# Module.net
KiCad netlist of a schematic drawn in Altium Designer
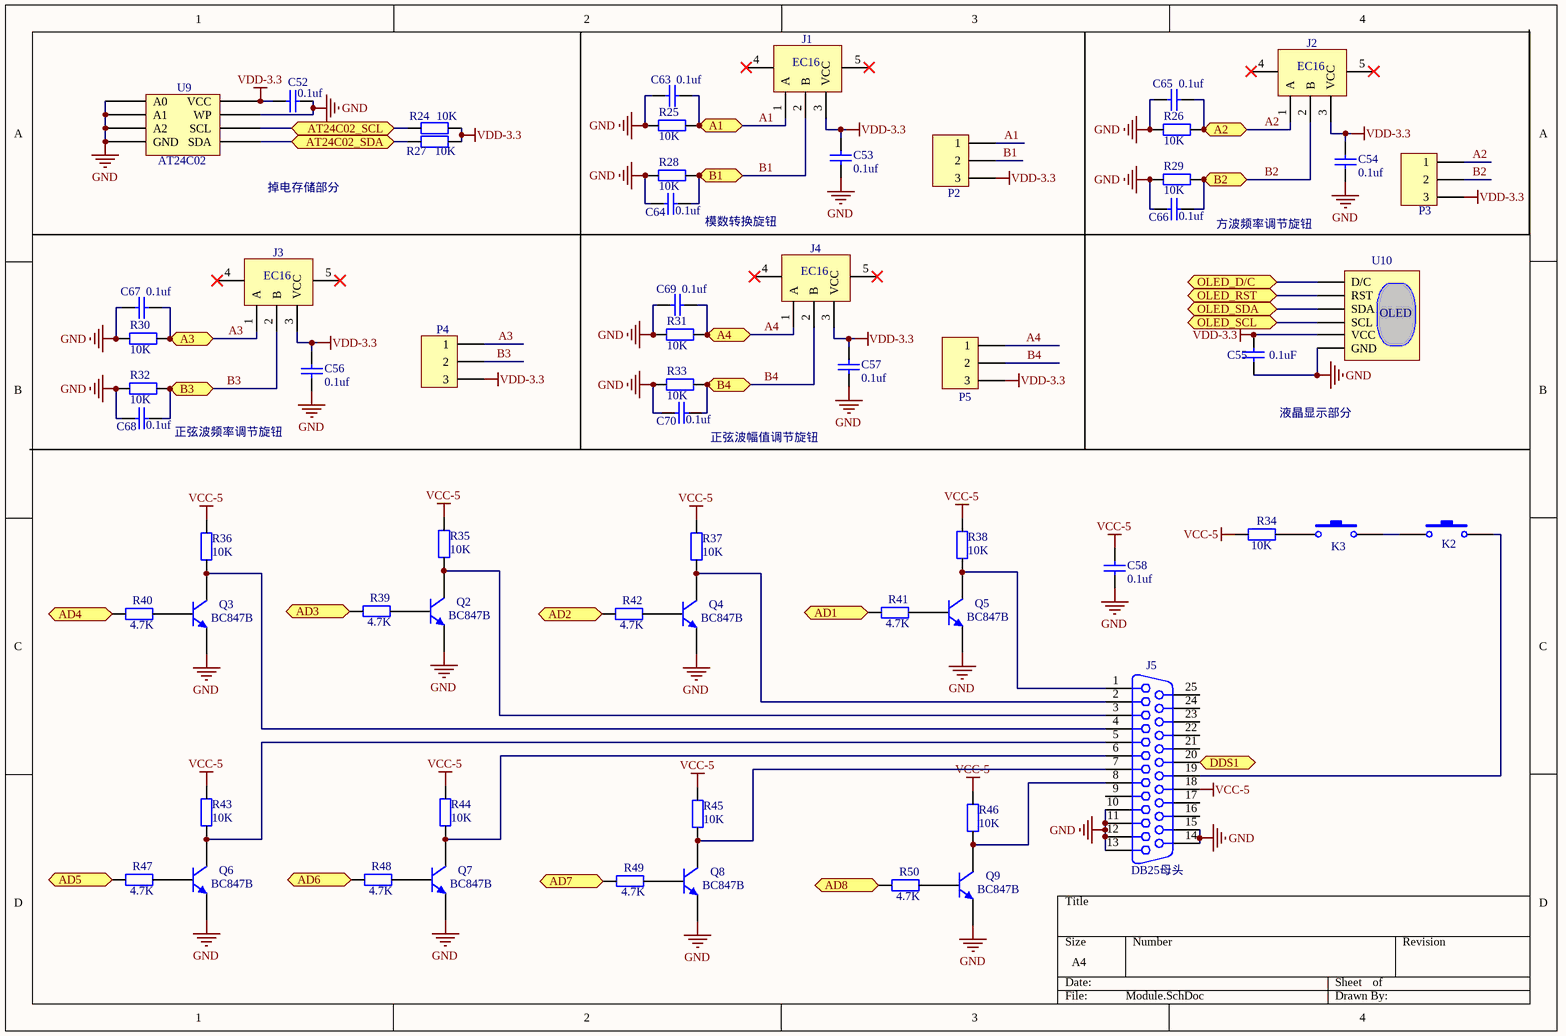
[diagram p0: Module.SchDoc]

(export (version "E")
  (design (tool "Eeschema 10.0.6"))
  (components
    (comp (ref "C52")
      (value "0.1uf")
      (footprint "0603")
      (fields (field (name "Comment") "Capacitor-0603"))
      (libsource (lib "原理图库") (part "Capacitor-0603"))
    )
    (comp (ref "C53")
      (value "0.1uf")
      (footprint "0603")
      (fields (field (name "Comment") "Capacitor-0603"))
      (libsource (lib "原理图库") (part "Capacitor-0603"))
    )
    (comp (ref "C54")
      (value "0.1uf")
      (footprint "0603")
      (fields (field (name "Comment") "Capacitor-0603"))
      (libsource (lib "原理图库") (part "Capacitor-0603"))
    )
    (comp (ref "C55")
      (value "0.1uF")
      (footprint "0603")
      (fields (field (name "Comment") "Capacitor-0805"))
      (libsource (lib "原理图库") (part "Capacitor-0805"))
    )
    (comp (ref "C56")
      (value "0.1uf")
      (footprint "0603")
      (fields (field (name "Comment") "Capacitor-0603"))
      (libsource (lib "原理图库") (part "Capacitor-0603"))
    )
    (comp (ref "C57")
      (value "0.1uf")
      (footprint "0603")
      (fields (field (name "Comment") "Capacitor-0603"))
      (libsource (lib "原理图库") (part "Capacitor-0603"))
    )
    (comp (ref "C58")
      (value "0.1uf")
      (footprint "0603")
      (fields (field (name "Comment") "Capacitor-0603"))
      (libsource (lib "原理图库") (part "Capacitor-0603"))
    )
    (comp (ref "C63")
      (value "0.1uf")
      (footprint "0603")
      (fields (field (name "Comment") "Capacitor-0603"))
      (libsource (lib "原理图库") (part "Capacitor-0603"))
    )
    (comp (ref "C64")
      (value "0.1uf")
      (footprint "0603")
      (fields (field (name "Comment") "Capacitor-0603"))
      (libsource (lib "原理图库") (part "Capacitor-0603"))
    )
    (comp (ref "C65")
      (value "0.1uf")
      (footprint "0603")
      (fields (field (name "Comment") "Capacitor-0603"))
      (libsource (lib "原理图库") (part "Capacitor-0603"))
    )
    (comp (ref "C66")
      (value "0.1uf")
      (footprint "0603")
      (fields (field (name "Comment") "Capacitor-0603"))
      (libsource (lib "原理图库") (part "Capacitor-0603"))
    )
    (comp (ref "C67")
      (value "0.1uf")
      (footprint "0603")
      (fields (field (name "Comment") "Capacitor-0603"))
      (libsource (lib "原理图库") (part "Capacitor-0603"))
    )
    (comp (ref "C68")
      (value "0.1uf")
      (footprint "0603")
      (fields (field (name "Comment") "Capacitor-0603"))
      (libsource (lib "原理图库") (part "Capacitor-0603"))
    )
    (comp (ref "C69")
      (value "0.1uf")
      (footprint "0603")
      (fields (field (name "Comment") "Capacitor-0603"))
      (libsource (lib "原理图库") (part "Capacitor-0603"))
    )
    (comp (ref "C70")
      (value "0.1uf")
      (footprint "0603")
      (fields (field (name "Comment") "Capacitor-0603"))
      (libsource (lib "原理图库") (part "Capacitor-0603"))
    )
    (comp (ref "J1")
      (value "EC16编码器")
      (footprint "EC16")
      (fields (field (name "NAME") "EC16"))
      (libsource (lib "原理图库") (part "EC16编码器"))
    )
    (comp (ref "J2")
      (value "EC16编码器")
      (footprint "EC16")
      (fields (field (name "NAME") "EC16"))
      (libsource (lib "原理图库") (part "EC16编码器"))
    )
    (comp (ref "J3")
      (value "EC16编码器")
      (footprint "EC16")
      (fields (field (name "NAME") "EC16"))
      (libsource (lib "原理图库") (part "EC16编码器"))
    )
    (comp (ref "J4")
      (value "EC16编码器")
      (footprint "EC16")
      (fields (field (name "NAME") "EC16"))
      (libsource (lib "原理图库") (part "EC16编码器"))
    )
    (comp (ref "J5")
      (value "DB25母头")
      (footprint "DB25母头")
      (fields (field (name "Comment") "DB25"))
      (libsource (lib "原理图库") (part "DB25"))
    )
    (comp (ref "K2") (value "按键") (footprint "2MM接线端子") (libsource (lib "原理图库") (part "按键")))
    (comp (ref "K3") (value "按键") (footprint "2MM接线端子") (libsource (lib "原理图库") (part "按键")))
    (comp (ref "P2") (value "端子3") (footprint "3MM接线端子") (libsource (lib "原理图库") (part "端子3")))
    (comp (ref "P3") (value "端子3") (footprint "3MM接线端子") (libsource (lib "原理图库") (part "端子3")))
    (comp (ref "P4") (value "端子3") (footprint "3MM接线端子") (libsource (lib "原理图库") (part "端子3")))
    (comp (ref "P5") (value "端子3") (footprint "3MM接线端子") (libsource (lib "原理图库") (part "端子3")))
    (comp (ref "Q2")
      (value "BC847")
      (footprint "BC847B")
      (fields (field (name "NAME") "BC847B"))
      (libsource (lib "原理图库") (part "BC847"))
    )
    (comp (ref "Q3")
      (value "BC847")
      (footprint "BC847B")
      (fields (field (name "NAME") "BC847B"))
      (libsource (lib "原理图库") (part "BC847"))
    )
    (comp (ref "Q4")
      (value "BC847")
      (footprint "BC847B")
      (fields (field (name "NAME") "BC847B"))
      (libsource (lib "原理图库") (part "BC847"))
    )
    (comp (ref "Q5")
      (value "BC847")
      (footprint "BC847B")
      (fields (field (name "NAME") "BC847B"))
      (libsource (lib "原理图库") (part "BC847"))
    )
    (comp (ref "Q6")
      (value "BC847")
      (footprint "BC847B")
      (fields (field (name "NAME") "BC847B"))
      (libsource (lib "原理图库") (part "BC847"))
    )
    (comp (ref "Q7")
      (value "BC847")
      (footprint "BC847B")
      (fields (field (name "NAME") "BC847B"))
      (libsource (lib "原理图库") (part "BC847"))
    )
    (comp (ref "Q8")
      (value "BC847")
      (footprint "BC847B")
      (fields (field (name "NAME") "BC847B"))
      (libsource (lib "原理图库") (part "BC847"))
    )
    (comp (ref "Q9")
      (value "BC847")
      (footprint "BC847B")
      (fields (field (name "NAME") "BC847B"))
      (libsource (lib "原理图库") (part "BC847"))
    )
    (comp (ref "R24")
      (value "10K")
      (footprint "0603")
      (fields (field (name "Comment") "Resistor-0603"))
      (libsource (lib "原理图库") (part "Resistor-0603"))
    )
    (comp (ref "R25")
      (value "10K")
      (footprint "0603")
      (fields (field (name "Comment") "Resistor-0603"))
      (libsource (lib "") (part "Resistor-0603_1"))
    )
    (comp (ref "R26")
      (value "10K")
      (footprint "0603")
      (fields (field (name "Comment") "Resistor-0603"))
      (libsource (lib "") (part "Resistor-0603_1"))
    )
    (comp (ref "R27")
      (value "10K")
      (footprint "0603")
      (fields (field (name "Comment") "Resistor-0603"))
      (libsource (lib "原理图库") (part "Resistor-0603"))
    )
    (comp (ref "R28")
      (value "10K")
      (footprint "0603")
      (fields (field (name "Comment") "Resistor-0603"))
      (libsource (lib "") (part "Resistor-0603_1"))
    )
    (comp (ref "R29")
      (value "10K")
      (footprint "0603")
      (fields (field (name "Comment") "Resistor-0603"))
      (libsource (lib "") (part "Resistor-0603_1"))
    )
    (comp (ref "R30")
      (value "10K")
      (footprint "0603")
      (fields (field (name "Comment") "Resistor-0603"))
      (libsource (lib "") (part "Resistor-0603_1"))
    )
    (comp (ref "R31")
      (value "10K")
      (footprint "0603")
      (fields (field (name "Comment") "Resistor-0603"))
      (libsource (lib "") (part "Resistor-0603_1"))
    )
    (comp (ref "R32")
      (value "10K")
      (footprint "0603")
      (fields (field (name "Comment") "Resistor-0603"))
      (libsource (lib "") (part "Resistor-0603_1"))
    )
    (comp (ref "R33")
      (value "10K")
      (footprint "0603")
      (fields (field (name "Comment") "Resistor-0603"))
      (libsource (lib "") (part "Resistor-0603_1"))
    )
    (comp (ref "R34")
      (value "10K")
      (footprint "0603")
      (fields (field (name "Comment") "Resistor-0603"))
      (libsource (lib "") (part "Resistor-0603_1"))
    )
    (comp (ref "R35")
      (value "10K")
      (footprint "0603")
      (fields (field (name "Comment") "Resistor-0603"))
      (libsource (lib "") (part "Resistor-0603_2"))
    )
    (comp (ref "R36")
      (value "10K")
      (footprint "0603")
      (fields (field (name "Comment") "Resistor-0603"))
      (libsource (lib "") (part "Resistor-0603_2"))
    )
    (comp (ref "R37")
      (value "10K")
      (footprint "0603")
      (fields (field (name "Comment") "Resistor-0603"))
      (libsource (lib "") (part "Resistor-0603_2"))
    )
    (comp (ref "R38")
      (value "10K")
      (footprint "0603")
      (fields (field (name "Comment") "Resistor-0603"))
      (libsource (lib "") (part "Resistor-0603_2"))
    )
    (comp (ref "R39")
      (value "4.7K")
      (footprint "0603")
      (fields (field (name "Comment") "Resistor-0603"))
      (libsource (lib "原理图库") (part "Resistor-0603"))
    )
    (comp (ref "R40")
      (value "4.7K")
      (footprint "0603")
      (fields (field (name "Comment") "Resistor-0603"))
      (libsource (lib "原理图库") (part "Resistor-0603"))
    )
    (comp (ref "R41")
      (value "4.7K")
      (footprint "0603")
      (fields (field (name "Comment") "Resistor-0603"))
      (libsource (lib "原理图库") (part "Resistor-0603"))
    )
    (comp (ref "R42")
      (value "4.7K")
      (footprint "0603")
      (fields (field (name "Comment") "Resistor-0603"))
      (libsource (lib "原理图库") (part "Resistor-0603"))
    )
    (comp (ref "R43")
      (value "10K")
      (footprint "0603")
      (fields (field (name "Comment") "Resistor-0603"))
      (libsource (lib "") (part "Resistor-0603_2"))
    )
    (comp (ref "R44")
      (value "10K")
      (footprint "0603")
      (fields (field (name "Comment") "Resistor-0603"))
      (libsource (lib "") (part "Resistor-0603_2"))
    )
    (comp (ref "R45")
      (value "10K")
      (footprint "0603")
      (fields (field (name "Comment") "Resistor-0603"))
      (libsource (lib "") (part "Resistor-0603_2"))
    )
    (comp (ref "R46")
      (value "10K")
      (footprint "0603")
      (fields (field (name "Comment") "Resistor-0603"))
      (libsource (lib "") (part "Resistor-0603_2"))
    )
    (comp (ref "R47")
      (value "4.7K")
      (footprint "0603")
      (fields (field (name "Comment") "Resistor-0603"))
      (libsource (lib "原理图库") (part "Resistor-0603"))
    )
    (comp (ref "R48")
      (value "4.7K")
      (footprint "0603")
      (fields (field (name "Comment") "Resistor-0603"))
      (libsource (lib "原理图库") (part "Resistor-0603"))
    )
    (comp (ref "R49")
      (value "4.7K")
      (footprint "0603")
      (fields (field (name "Comment") "Resistor-0603"))
      (libsource (lib "原理图库") (part "Resistor-0603"))
    )
    (comp (ref "R50")
      (value "4.7K")
      (footprint "0603")
      (fields (field (name "Comment") "Resistor-0603"))
      (libsource (lib "原理图库") (part "Resistor-0603"))
    )
    (comp (ref "U9")
      (value "AT24C02")
      (footprint "AT24C02")
      (fields (field (name "NAME") "AT24C02"))
      (libsource (lib "原理图库") (part "AT24C02"))
    )
    (comp (ref "U10")
      (value "OLED")
      (footprint "OLED")
      (fields (field (name "NAME") "OLED"))
      (libsource (lib "原理图库") (part "OLED"))
    )
  )
  (nets
    (net (code "1") (name "/A1") (class "Default")
      (node (ref "C63") (pin "2") (pinfunction "2_2") (pintype "passive"))
      (node (ref "J1") (pin "1") (pinfunction "A_1") (pintype "passive"))
      (node (ref "P2") (pin "1") (pinfunction "1_1") (pintype "passive"))
      (node (ref "R25") (pin "2") (pinfunction "2_2") (pintype "passive"))
    )
    (net (code "2") (name "/A2") (class "Default")
      (node (ref "C65") (pin "2") (pinfunction "2_2") (pintype "passive"))
      (node (ref "J2") (pin "1") (pinfunction "A_1") (pintype "passive"))
      (node (ref "P3") (pin "1") (pinfunction "1_1") (pintype "passive"))
      (node (ref "R26") (pin "2") (pinfunction "2_2") (pintype "passive"))
    )
    (net (code "3") (name "/A3") (class "Default")
      (node (ref "C67") (pin "2") (pinfunction "2_2") (pintype "passive"))
      (node (ref "J3") (pin "1") (pinfunction "A_1") (pintype "passive"))
      (node (ref "P4") (pin "1") (pinfunction "1_1") (pintype "passive"))
      (node (ref "R30") (pin "2") (pinfunction "2_2") (pintype "passive"))
    )
    (net (code "4") (name "/A4") (class "Default")
      (node (ref "C69") (pin "2") (pinfunction "2_2") (pintype "passive"))
      (node (ref "J4") (pin "1") (pinfunction "A_1") (pintype "passive"))
      (node (ref "P5") (pin "1") (pinfunction "1_1") (pintype "passive"))
      (node (ref "R31") (pin "2") (pinfunction "2_2") (pintype "passive"))
    )
    (net (code "5") (name "/AD1") (class "Default")
      (node (ref "R41") (pin "2") (pinfunction "2_2") (pintype "passive"))
    )
    (net (code "6") (name "/AD2") (class "Default")
      (node (ref "R42") (pin "2") (pinfunction "2_2") (pintype "passive"))
    )
    (net (code "7") (name "/AD3") (class "Default")
      (node (ref "R39") (pin "2") (pinfunction "2_2") (pintype "passive"))
    )
    (net (code "8") (name "/AD4") (class "Default")
      (node (ref "R40") (pin "2") (pinfunction "2_2") (pintype "passive"))
    )
    (net (code "9") (name "/AD5") (class "Default")
      (node (ref "R47") (pin "2") (pinfunction "2_2") (pintype "passive"))
    )
    (net (code "10") (name "/AD6") (class "Default")
      (node (ref "R48") (pin "2") (pinfunction "2_2") (pintype "passive"))
    )
    (net (code "11") (name "/AD7") (class "Default")
      (node (ref "R49") (pin "2") (pinfunction "2_2") (pintype "passive"))
    )
    (net (code "12") (name "/AD8") (class "Default")
      (node (ref "R50") (pin "2") (pinfunction "2_2") (pintype "passive"))
    )
    (net (code "13") (name "/AT24C02_SCL") (class "Default")
      (node (ref "R24") (pin "2") (pinfunction "2_2") (pintype "passive"))
      (node (ref "U9") (pin "6") (pinfunction "SCL_6") (pintype "passive"))
    )
    (net (code "14") (name "/AT24C02_SDA") (class "Default")
      (node (ref "R27") (pin "2") (pinfunction "2_2") (pintype "passive"))
      (node (ref "U9") (pin "5") (pinfunction "SDA_5") (pintype "passive"))
    )
    (net (code "15") (name "/B1") (class "Default")
      (node (ref "C64") (pin "2") (pinfunction "2_2") (pintype "passive"))
      (node (ref "J1") (pin "2") (pinfunction "B_2") (pintype "passive"))
      (node (ref "P2") (pin "2") (pinfunction "2_2") (pintype "passive"))
      (node (ref "R28") (pin "2") (pinfunction "2_2") (pintype "passive"))
    )
    (net (code "16") (name "/B2") (class "Default")
      (node (ref "C66") (pin "2") (pinfunction "2_2") (pintype "passive"))
      (node (ref "J2") (pin "2") (pinfunction "B_2") (pintype "passive"))
      (node (ref "P3") (pin "2") (pinfunction "2_2") (pintype "passive"))
      (node (ref "R29") (pin "2") (pinfunction "2_2") (pintype "passive"))
    )
    (net (code "17") (name "/B3") (class "Default")
      (node (ref "C68") (pin "2") (pinfunction "2_2") (pintype "passive"))
      (node (ref "J3") (pin "2") (pinfunction "B_2") (pintype "passive"))
      (node (ref "P4") (pin "2") (pinfunction "2_2") (pintype "passive"))
      (node (ref "R32") (pin "2") (pinfunction "2_2") (pintype "passive"))
    )
    (net (code "18") (name "/B4") (class "Default")
      (node (ref "C70") (pin "2") (pinfunction "2_2") (pintype "passive"))
      (node (ref "J4") (pin "2") (pinfunction "B_2") (pintype "passive"))
      (node (ref "P5") (pin "2") (pinfunction "2_2") (pintype "passive"))
      (node (ref "R33") (pin "2") (pinfunction "2_2") (pintype "passive"))
    )
    (net (code "19") (name "/DDS1") (class "Default")
      (node (ref "J5") (pin "20") (pinfunction "20_20") (pintype "passive"))
    )
    (net (code "20") (name "/OLED_D{slash}C") (class "Default")
      (node (ref "U10") (pin "6") (pinfunction "D/C_6") (pintype "passive"))
    )
    (net (code "21") (name "/OLED_RST") (class "Default")
      (node (ref "U10") (pin "5") (pinfunction "RST_5") (pintype "passive"))
    )
    (net (code "22") (name "/OLED_SCL") (class "Default")
      (node (ref "U10") (pin "3") (pinfunction "SCL_3") (pintype "passive"))
    )
    (net (code "23") (name "/OLED_SDA") (class "Default")
      (node (ref "U10") (pin "4") (pinfunction "SDA_4") (pintype "passive"))
    )
    (net (code "24") (name "GND") (class "Default")
      (node (ref "C52") (pin "1") (pinfunction "1_1") (pintype "passive"))
      (node (ref "C53") (pin "2") (pinfunction "2_2") (pintype "passive"))
      (node (ref "C54") (pin "2") (pinfunction "2_2") (pintype "passive"))
      (node (ref "C55") (pin "1") (pinfunction "1_1") (pintype "passive"))
      (node (ref "C56") (pin "2") (pinfunction "2_2") (pintype "passive"))
      (node (ref "C57") (pin "2") (pinfunction "2_2") (pintype "passive"))
      (node (ref "C58") (pin "2") (pinfunction "2_2") (pintype "passive"))
      (node (ref "C63") (pin "1") (pinfunction "1_1") (pintype "passive"))
      (node (ref "C64") (pin "1") (pinfunction "1_1") (pintype "passive"))
      (node (ref "C65") (pin "1") (pinfunction "1_1") (pintype "passive"))
      (node (ref "C66") (pin "1") (pinfunction "1_1") (pintype "passive"))
      (node (ref "C67") (pin "1") (pinfunction "1_1") (pintype "passive"))
      (node (ref "C68") (pin "1") (pinfunction "1_1") (pintype "passive"))
      (node (ref "C69") (pin "1") (pinfunction "1_1") (pintype "passive"))
      (node (ref "C70") (pin "1") (pinfunction "1_1") (pintype "passive"))
      (node (ref "J5") (pin "10") (pinfunction "10_10") (pintype "passive"))
      (node (ref "J5") (pin "11") (pinfunction "11_11") (pintype "passive"))
      (node (ref "J5") (pin "12") (pinfunction "12_12") (pintype "passive"))
      (node (ref "J5") (pin "13") (pinfunction "13_13") (pintype "passive"))
      (node (ref "J5") (pin "14") (pinfunction "14_14") (pintype "passive"))
      (node (ref "J5") (pin "15") (pinfunction "15_15") (pintype "passive"))
      (node (ref "Q2") (pin "1") (pinfunction "E_1") (pintype "passive"))
      (node (ref "Q3") (pin "1") (pinfunction "E_1") (pintype "passive"))
      (node (ref "Q4") (pin "1") (pinfunction "E_1") (pintype "passive"))
      (node (ref "Q5") (pin "1") (pinfunction "E_1") (pintype "passive"))
      (node (ref "Q6") (pin "1") (pinfunction "E_1") (pintype "passive"))
      (node (ref "Q7") (pin "1") (pinfunction "E_1") (pintype "passive"))
      (node (ref "Q8") (pin "1") (pinfunction "E_1") (pintype "passive"))
      (node (ref "Q9") (pin "1") (pinfunction "E_1") (pintype "passive"))
      (node (ref "R25") (pin "1") (pinfunction "1_1") (pintype "passive"))
      (node (ref "R26") (pin "1") (pinfunction "1_1") (pintype "passive"))
      (node (ref "R28") (pin "1") (pinfunction "1_1") (pintype "passive"))
      (node (ref "R29") (pin "1") (pinfunction "1_1") (pintype "passive"))
      (node (ref "R30") (pin "1") (pinfunction "1_1") (pintype "passive"))
      (node (ref "R31") (pin "1") (pinfunction "1_1") (pintype "passive"))
      (node (ref "R32") (pin "1") (pinfunction "1_1") (pintype "passive"))
      (node (ref "R33") (pin "1") (pinfunction "1_1") (pintype "passive"))
      (node (ref "U10") (pin "1") (pinfunction "GND_1") (pintype "passive"))
      (node (ref "U9") (pin "1") (pinfunction "A0_1") (pintype "passive"))
      (node (ref "U9") (pin "2") (pinfunction "A1_2") (pintype "passive"))
      (node (ref "U9") (pin "3") (pinfunction "A2_3") (pintype "passive"))
      (node (ref "U9") (pin "4") (pinfunction "GND_4") (pintype "passive"))
      (node (ref "U9") (pin "7") (pinfunction "WP_7") (pintype "passive"))
    )
    (net (code "25") (name "Net-(J5-Pad19)") (class "Default")
      (node (ref "J5") (pin "19") (pinfunction "19_19") (pintype "passive"))
      (node (ref "K2") (pin "2") (pinfunction "2_2") (pintype "passive"))
    )
    (net (code "26") (name "Net-(K2-Pad1)") (class "Default")
      (node (ref "K2") (pin "1") (pinfunction "1_1") (pintype "passive"))
      (node (ref "K3") (pin "2") (pinfunction "2_2") (pintype "passive"))
    )
    (net (code "27") (name "Net-(K3-Pad1)") (class "Default")
      (node (ref "K3") (pin "1") (pinfunction "1_1") (pintype "passive"))
      (node (ref "R34") (pin "2") (pinfunction "2_2") (pintype "passive"))
    )
    (net (code "28") (name "Net-(Q2-B)") (class "Default")
      (node (ref "Q2") (pin "2") (pinfunction "B_2") (pintype "passive"))
      (node (ref "R39") (pin "1") (pinfunction "1_1") (pintype "passive"))
    )
    (net (code "29") (name "Net-(Q2-C)") (class "Default")
      (node (ref "J5") (pin "3") (pinfunction "3_3") (pintype "passive"))
      (node (ref "Q2") (pin "3") (pinfunction "C_3") (pintype "passive"))
      (node (ref "R35") (pin "1") (pinfunction "1_1") (pintype "passive"))
    )
    (net (code "30") (name "Net-(Q3-B)") (class "Default")
      (node (ref "Q3") (pin "2") (pinfunction "B_2") (pintype "passive"))
      (node (ref "R40") (pin "1") (pinfunction "1_1") (pintype "passive"))
    )
    (net (code "31") (name "Net-(Q3-C)") (class "Default")
      (node (ref "J5") (pin "4") (pinfunction "4_4") (pintype "passive"))
      (node (ref "Q3") (pin "3") (pinfunction "C_3") (pintype "passive"))
      (node (ref "R36") (pin "1") (pinfunction "1_1") (pintype "passive"))
    )
    (net (code "32") (name "Net-(Q4-B)") (class "Default")
      (node (ref "Q4") (pin "2") (pinfunction "B_2") (pintype "passive"))
      (node (ref "R42") (pin "1") (pinfunction "1_1") (pintype "passive"))
    )
    (net (code "33") (name "Net-(Q4-C)") (class "Default")
      (node (ref "J5") (pin "2") (pinfunction "2_2") (pintype "passive"))
      (node (ref "Q4") (pin "3") (pinfunction "C_3") (pintype "passive"))
      (node (ref "R37") (pin "1") (pinfunction "1_1") (pintype "passive"))
    )
    (net (code "34") (name "Net-(Q5-B)") (class "Default")
      (node (ref "Q5") (pin "2") (pinfunction "B_2") (pintype "passive"))
      (node (ref "R41") (pin "1") (pinfunction "1_1") (pintype "passive"))
    )
    (net (code "35") (name "Net-(Q5-C)") (class "Default")
      (node (ref "J5") (pin "1") (pinfunction "1_1") (pintype "passive"))
      (node (ref "Q5") (pin "3") (pinfunction "C_3") (pintype "passive"))
      (node (ref "R38") (pin "1") (pinfunction "1_1") (pintype "passive"))
    )
    (net (code "36") (name "Net-(Q6-B)") (class "Default")
      (node (ref "Q6") (pin "2") (pinfunction "B_2") (pintype "passive"))
      (node (ref "R47") (pin "1") (pinfunction "1_1") (pintype "passive"))
    )
    (net (code "37") (name "Net-(Q6-C)") (class "Default")
      (node (ref "J5") (pin "5") (pinfunction "5_5") (pintype "passive"))
      (node (ref "Q6") (pin "3") (pinfunction "C_3") (pintype "passive"))
      (node (ref "R43") (pin "1") (pinfunction "1_1") (pintype "passive"))
    )
    (net (code "38") (name "Net-(Q7-B)") (class "Default")
      (node (ref "Q7") (pin "2") (pinfunction "B_2") (pintype "passive"))
      (node (ref "R48") (pin "1") (pinfunction "1_1") (pintype "passive"))
    )
    (net (code "39") (name "Net-(Q7-C)") (class "Default")
      (node (ref "J5") (pin "6") (pinfunction "6_6") (pintype "passive"))
      (node (ref "Q7") (pin "3") (pinfunction "C_3") (pintype "passive"))
      (node (ref "R44") (pin "1") (pinfunction "1_1") (pintype "passive"))
    )
    (net (code "40") (name "Net-(Q8-B)") (class "Default")
      (node (ref "Q8") (pin "2") (pinfunction "B_2") (pintype "passive"))
      (node (ref "R49") (pin "1") (pinfunction "1_1") (pintype "passive"))
    )
    (net (code "41") (name "Net-(Q8-C)") (class "Default")
      (node (ref "J5") (pin "7") (pinfunction "7_7") (pintype "passive"))
      (node (ref "Q8") (pin "3") (pinfunction "C_3") (pintype "passive"))
      (node (ref "R45") (pin "1") (pinfunction "1_1") (pintype "passive"))
    )
    (net (code "42") (name "Net-(Q9-B)") (class "Default")
      (node (ref "Q9") (pin "2") (pinfunction "B_2") (pintype "passive"))
      (node (ref "R50") (pin "1") (pinfunction "1_1") (pintype "passive"))
    )
    (net (code "43") (name "Net-(Q9-C)") (class "Default")
      (node (ref "J5") (pin "8") (pinfunction "8_8") (pintype "passive"))
      (node (ref "Q9") (pin "3") (pinfunction "C_3") (pintype "passive"))
      (node (ref "R46") (pin "1") (pinfunction "1_1") (pintype "passive"))
    )
    (net (code "44") (name "VCC-5") (class "Default")
      (node (ref "C58") (pin "1") (pinfunction "1_1") (pintype "passive"))
      (node (ref "J5") (pin "18") (pinfunction "18_18") (pintype "passive"))
      (node (ref "R34") (pin "1") (pinfunction "1_1") (pintype "passive"))
      (node (ref "R35") (pin "2") (pinfunction "2_2") (pintype "passive"))
      (node (ref "R36") (pin "2") (pinfunction "2_2") (pintype "passive"))
      (node (ref "R37") (pin "2") (pinfunction "2_2") (pintype "passive"))
      (node (ref "R38") (pin "2") (pinfunction "2_2") (pintype "passive"))
      (node (ref "R43") (pin "2") (pinfunction "2_2") (pintype "passive"))
      (node (ref "R44") (pin "2") (pinfunction "2_2") (pintype "passive"))
      (node (ref "R45") (pin "2") (pinfunction "2_2") (pintype "passive"))
      (node (ref "R46") (pin "2") (pinfunction "2_2") (pintype "passive"))
    )
    (net (code "45") (name "VDD-3.3") (class "Default")
      (node (ref "C52") (pin "2") (pinfunction "2_2") (pintype "passive"))
      (node (ref "C53") (pin "1") (pinfunction "1_1") (pintype "passive"))
      (node (ref "C54") (pin "1") (pinfunction "1_1") (pintype "passive"))
      (node (ref "C55") (pin "2") (pinfunction "2_2") (pintype "passive"))
      (node (ref "C56") (pin "1") (pinfunction "1_1") (pintype "passive"))
      (node (ref "C57") (pin "1") (pinfunction "1_1") (pintype "passive"))
      (node (ref "J1") (pin "3") (pinfunction "VCC_3") (pintype "passive"))
      (node (ref "J2") (pin "3") (pinfunction "VCC_3") (pintype "passive"))
      (node (ref "J3") (pin "3") (pinfunction "VCC_3") (pintype "passive"))
      (node (ref "J4") (pin "3") (pinfunction "VCC_3") (pintype "passive"))
      (node (ref "P2") (pin "3") (pinfunction "3_3") (pintype "passive"))
      (node (ref "P3") (pin "3") (pinfunction "3_3") (pintype "passive"))
      (node (ref "P4") (pin "3") (pinfunction "3_3") (pintype "passive"))
      (node (ref "P5") (pin "3") (pinfunction "3_3") (pintype "passive"))
      (node (ref "R24") (pin "1") (pinfunction "1_1") (pintype "passive"))
      (node (ref "R27") (pin "1") (pinfunction "1_1") (pintype "passive"))
      (node (ref "U10") (pin "2") (pinfunction "VCC_2") (pintype "passive"))
      (node (ref "U9") (pin "8") (pinfunction "VCC_8") (pintype "passive"))
    )
    (net (code "46") (name "unconnected-(J1-Pad4)") (class "Default")
      (node (ref "J1") (pin "4") (pinfunction "4_4") (pintype "passive+no_connect"))
    )
    (net (code "47") (name "unconnected-(J1-Pad5)") (class "Default")
      (node (ref "J1") (pin "5") (pinfunction "5_5") (pintype "passive+no_connect"))
    )
    (net (code "48") (name "unconnected-(J2-Pad4)") (class "Default")
      (node (ref "J2") (pin "4") (pinfunction "4_4") (pintype "passive+no_connect"))
    )
    (net (code "49") (name "unconnected-(J2-Pad5)") (class "Default")
      (node (ref "J2") (pin "5") (pinfunction "5_5") (pintype "passive+no_connect"))
    )
    (net (code "50") (name "unconnected-(J3-Pad4)") (class "Default")
      (node (ref "J3") (pin "4") (pinfunction "4_4") (pintype "passive+no_connect"))
    )
    (net (code "51") (name "unconnected-(J3-Pad5)") (class "Default")
      (node (ref "J3") (pin "5") (pinfunction "5_5") (pintype "passive+no_connect"))
    )
    (net (code "52") (name "unconnected-(J4-Pad4)") (class "Default")
      (node (ref "J4") (pin "4") (pinfunction "4_4") (pintype "passive+no_connect"))
    )
    (net (code "53") (name "unconnected-(J4-Pad5)") (class "Default")
      (node (ref "J4") (pin "5") (pinfunction "5_5") (pintype "passive+no_connect"))
    )
    (net (code "54") (name "unconnected-(J5-Pad9)") (class "Default")
      (node (ref "J5") (pin "9") (pinfunction "9_9") (pintype "passive"))
    )
    (net (code "55") (name "unconnected-(J5-Pad16)") (class "Default")
      (node (ref "J5") (pin "16") (pinfunction "16_16") (pintype "passive"))
    )
    (net (code "56") (name "unconnected-(J5-Pad17)") (class "Default")
      (node (ref "J5") (pin "17") (pinfunction "17_17") (pintype "passive"))
    )
    (net (code "57") (name "unconnected-(J5-Pad21)") (class "Default")
      (node (ref "J5") (pin "21") (pinfunction "21_21") (pintype "passive"))
    )
    (net (code "58") (name "unconnected-(J5-Pad22)") (class "Default")
      (node (ref "J5") (pin "22") (pinfunction "22_22") (pintype "passive"))
    )
    (net (code "59") (name "unconnected-(J5-Pad23)") (class "Default")
      (node (ref "J5") (pin "23") (pinfunction "23_23") (pintype "passive"))
    )
    (net (code "60") (name "unconnected-(J5-Pad24)") (class "Default")
      (node (ref "J5") (pin "24") (pinfunction "24_24") (pintype "passive"))
    )
    (net (code "61") (name "unconnected-(J5-Pad25)") (class "Default")
      (node (ref "J5") (pin "25") (pinfunction "25_25") (pintype "passive"))
    )
  )
)
